# 11-LedIndicators.net
KiCad netlist of a schematic drawn in Altium Designer
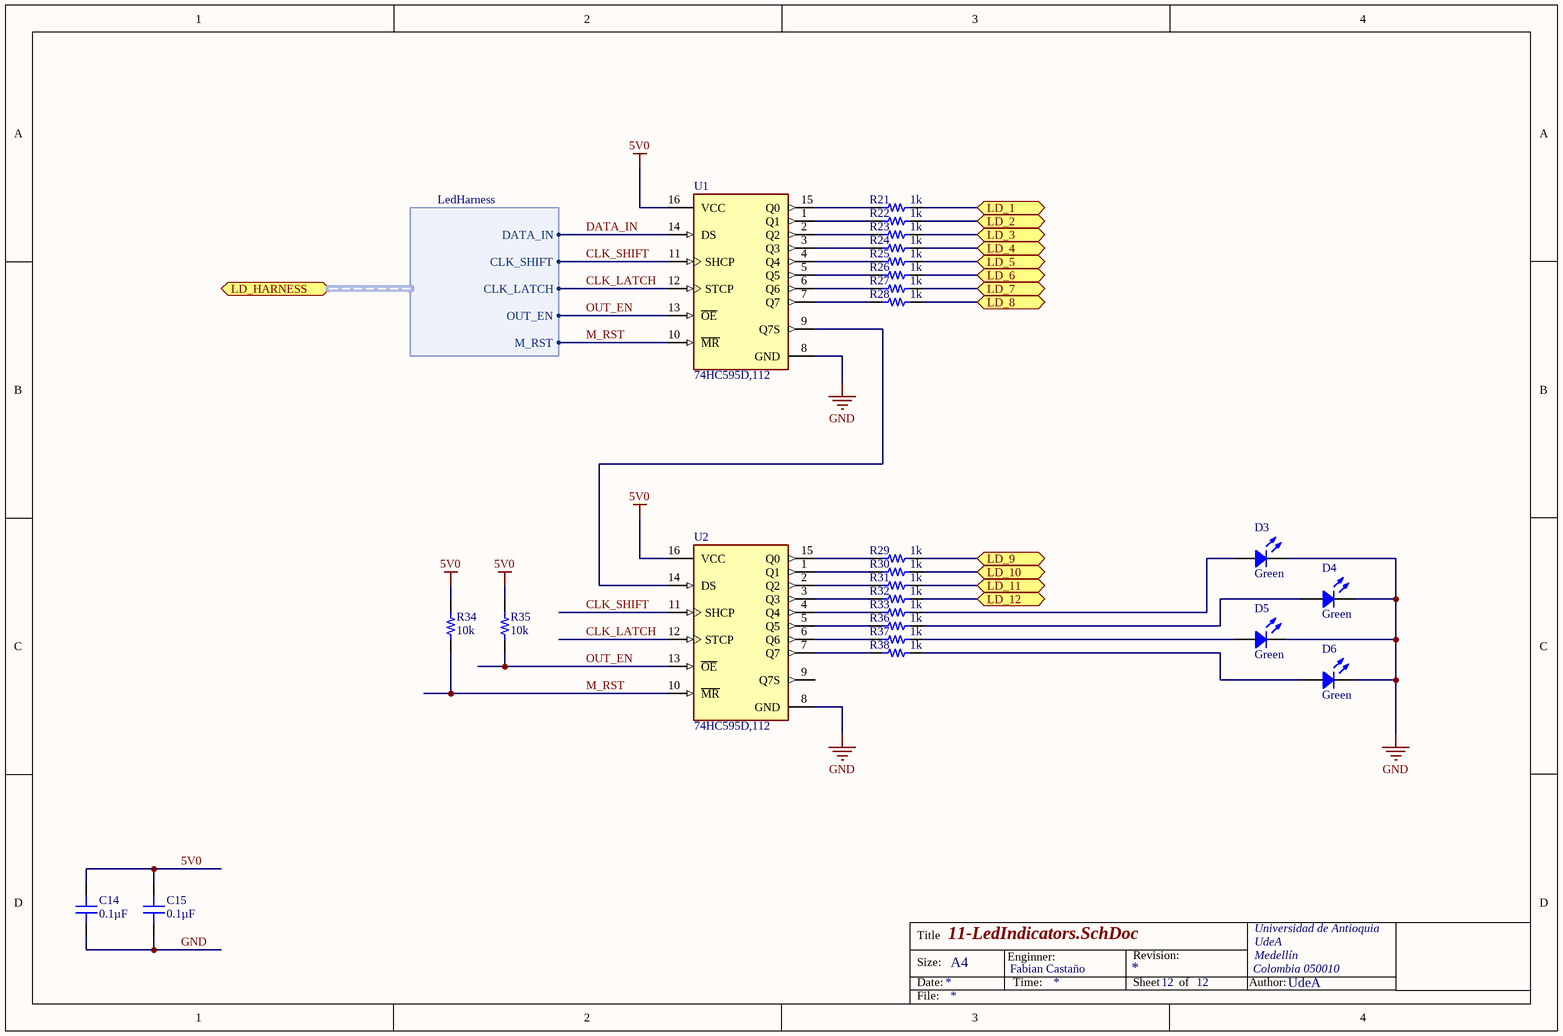
[diagram p0: 11-LedIndicators.SchDoc]

(export (version "E")
  (design (tool "Eeschema 10.0.6"))
  (components
    (comp (ref "C14")
      (value "0.1µF")
      (footprint "CAP 0805_2012")
      (description "CAP CER 0.1UF 50V X7R 0805")
      (fields (field (name "PART NUMBER") "C0805C104M5RACAUTO") (field (name "MANUFACTURER") "KEMET"))
      (libsource (lib "Celestial Altium Library - altium_library") (part "Capacitor"))
    )
    (comp (ref "C15")
      (value "0.1µF")
      (footprint "CAP 0805_2012")
      (description "CAP CER 0.1UF 50V X7R 0805")
      (fields (field (name "PART NUMBER") "C0805C104M5RACAUTO") (field (name "MANUFACTURER") "KEMET"))
      (libsource (lib "Celestial Altium Library - altium_library") (part "Capacitor"))
    )
    (comp (ref "D3")
      (value "Green")
      (footprint "LED 0805_2012 YELLOW")
      (description "LED YELLOW CLEAR CHIP SMD")
      (fields
        (field (name "PART NUMBER") "APT2012SYCK")
        (field (name "MANUFACTURER") "Kingbright")
        (field (name "LASTUPDATED") "12/04/2022 10:52:50 p. m.")
      )
      (libsource (lib "Celestial Altium Library - altium_library") (part "LED"))
    )
    (comp (ref "D4")
      (value "Green")
      (footprint "LED 0805_2012 YELLOW")
      (description "LED YELLOW CLEAR CHIP SMD")
      (fields
        (field (name "PART NUMBER") "APT2012SYCK")
        (field (name "MANUFACTURER") "Kingbright")
        (field (name "LASTUPDATED") "12/04/2022 10:52:50 p. m.")
      )
      (libsource (lib "Celestial Altium Library - altium_library") (part "LED"))
    )
    (comp (ref "D5")
      (value "Green")
      (footprint "LED 0805_2012 YELLOW")
      (description "LED YELLOW CLEAR CHIP SMD")
      (fields
        (field (name "PART NUMBER") "APT2012SYCK")
        (field (name "MANUFACTURER") "Kingbright")
        (field (name "LASTUPDATED") "12/04/2022 10:52:50 p. m.")
      )
      (libsource (lib "Celestial Altium Library - altium_library") (part "LED"))
    )
    (comp (ref "D6")
      (value "Green")
      (footprint "LED 0805_2012 YELLOW")
      (description "LED YELLOW CLEAR CHIP SMD")
      (fields
        (field (name "PART NUMBER") "APT2012SYCK")
        (field (name "MANUFACTURER") "Kingbright")
        (field (name "LASTUPDATED") "12/04/2022 10:52:50 p. m.")
      )
      (libsource (lib "Celestial Altium Library - altium_library") (part "LED"))
    )
    (comp (ref "R21")
      (value "1k")
      (footprint "RES 0805_2012")
      (description "RES SMD 1.47K OHM 1% 1/8W 0805")
      (fields (field (name "PART NUMBER") "RC0805FR-071K47L") (field (name "MANUFACTURER") "Yageo"))
      (libsource (lib "Celestial Altium Library - altium_library") (part "Resistor"))
    )
    (comp (ref "R22")
      (value "1k")
      (footprint "RES 0805_2012")
      (description "RES SMD 1.47K OHM 1% 1/8W 0805")
      (fields (field (name "PART NUMBER") "RC0805FR-071K47L") (field (name "MANUFACTURER") "Yageo"))
      (libsource (lib "Celestial Altium Library - altium_library") (part "Resistor"))
    )
    (comp (ref "R23")
      (value "1k")
      (footprint "RES 0805_2012")
      (description "RES SMD 1.47K OHM 1% 1/8W 0805")
      (fields (field (name "PART NUMBER") "RC0805FR-071K47L") (field (name "MANUFACTURER") "Yageo"))
      (libsource (lib "Celestial Altium Library - altium_library") (part "Resistor"))
    )
    (comp (ref "R24")
      (value "1k")
      (footprint "RES 0805_2012")
      (description "RES SMD 1.47K OHM 1% 1/8W 0805")
      (fields (field (name "PART NUMBER") "RC0805FR-071K47L") (field (name "MANUFACTURER") "Yageo"))
      (libsource (lib "Celestial Altium Library - altium_library") (part "Resistor"))
    )
    (comp (ref "R25")
      (value "1k")
      (footprint "RES 0805_2012")
      (description "RES SMD 1.47K OHM 1% 1/8W 0805")
      (fields (field (name "PART NUMBER") "RC0805FR-071K47L") (field (name "MANUFACTURER") "Yageo"))
      (libsource (lib "Celestial Altium Library - altium_library") (part "Resistor"))
    )
    (comp (ref "R26")
      (value "1k")
      (footprint "RES 0805_2012")
      (description "RES SMD 1.47K OHM 1% 1/8W 0805")
      (fields (field (name "PART NUMBER") "RC0805FR-071K47L") (field (name "MANUFACTURER") "Yageo"))
      (libsource (lib "Celestial Altium Library - altium_library") (part "Resistor"))
    )
    (comp (ref "R27")
      (value "1k")
      (footprint "RES 0805_2012")
      (description "RES SMD 1.47K OHM 1% 1/8W 0805")
      (fields (field (name "PART NUMBER") "RC0805FR-071K47L") (field (name "MANUFACTURER") "Yageo"))
      (libsource (lib "Celestial Altium Library - altium_library") (part "Resistor"))
    )
    (comp (ref "R28")
      (value "1k")
      (footprint "RES 0805_2012")
      (description "RES SMD 1.47K OHM 1% 1/8W 0805")
      (fields (field (name "PART NUMBER") "RC0805FR-071K47L") (field (name "MANUFACTURER") "Yageo"))
      (libsource (lib "Celestial Altium Library - altium_library") (part "Resistor"))
    )
    (comp (ref "R29")
      (value "1k")
      (footprint "RES 0805_2012")
      (description "RES SMD 1.47K OHM 1% 1/8W 0805")
      (fields (field (name "PART NUMBER") "RC0805FR-071K47L") (field (name "MANUFACTURER") "Yageo"))
      (libsource (lib "Celestial Altium Library - altium_library") (part "Resistor"))
    )
    (comp (ref "R30")
      (value "1k")
      (footprint "RES 0805_2012")
      (description "RES SMD 1.47K OHM 1% 1/8W 0805")
      (fields (field (name "PART NUMBER") "RC0805FR-071K47L") (field (name "MANUFACTURER") "Yageo"))
      (libsource (lib "Celestial Altium Library - altium_library") (part "Resistor"))
    )
    (comp (ref "R31")
      (value "1k")
      (footprint "RES 0805_2012")
      (description "RES SMD 1.47K OHM 1% 1/8W 0805")
      (fields (field (name "PART NUMBER") "RC0805FR-071K47L") (field (name "MANUFACTURER") "Yageo"))
      (libsource (lib "Celestial Altium Library - altium_library") (part "Resistor"))
    )
    (comp (ref "R32")
      (value "1k")
      (footprint "RES 0805_2012")
      (description "RES SMD 1.47K OHM 1% 1/8W 0805")
      (fields (field (name "PART NUMBER") "RC0805FR-071K47L") (field (name "MANUFACTURER") "Yageo"))
      (libsource (lib "Celestial Altium Library - altium_library") (part "Resistor"))
    )
    (comp (ref "R33")
      (value "1k")
      (footprint "RES 0805_2012")
      (description "RES SMD 1.47K OHM 1% 1/8W 0805")
      (fields (field (name "PART NUMBER") "RC0805FR-071K47L") (field (name "MANUFACTURER") "Yageo"))
      (libsource (lib "Celestial Altium Library - altium_library") (part "Resistor"))
    )
    (comp (ref "R34")
      (value "10k")
      (footprint "RES 0805_2012")
      (description "RES SMD 1.47K OHM 1% 1/8W 0805")
      (fields (field (name "PART NUMBER") "RC0805FR-071K47L") (field (name "MANUFACTURER") "Yageo"))
      (libsource (lib "Celestial Altium Library - altium_library") (part "Resistor"))
    )
    (comp (ref "R35")
      (value "10k")
      (footprint "RES 0805_2012")
      (description "RES SMD 1.47K OHM 1% 1/8W 0805")
      (fields (field (name "PART NUMBER") "RC0805FR-071K47L") (field (name "MANUFACTURER") "Yageo"))
      (libsource (lib "Celestial Altium Library - altium_library") (part "Resistor"))
    )
    (comp (ref "R36")
      (value "1k")
      (footprint "RES 0805_2012")
      (description "RES SMD 1.47K OHM 1% 1/8W 0805")
      (fields (field (name "PART NUMBER") "RC0805FR-071K47L") (field (name "MANUFACTURER") "Yageo"))
      (libsource (lib "Celestial Altium Library - altium_library") (part "Resistor"))
    )
    (comp (ref "R37")
      (value "1k")
      (footprint "RES 0805_2012")
      (description "RES SMD 1.47K OHM 1% 1/8W 0805")
      (fields (field (name "PART NUMBER") "RC0805FR-071K47L") (field (name "MANUFACTURER") "Yageo"))
      (libsource (lib "Celestial Altium Library - altium_library") (part "Resistor"))
    )
    (comp (ref "R38")
      (value "1k")
      (footprint "RES 0805_2012")
      (description "RES SMD 1.47K OHM 1% 1/8W 0805")
      (fields (field (name "PART NUMBER") "RC0805FR-071K47L") (field (name "MANUFACTURER") "Yageo"))
      (libsource (lib "Celestial Altium Library - altium_library") (part "Resistor"))
    )
    (comp (ref "U1")
      (value "74HC595D,112")
      (footprint "FP-SOT109-1-MFG")
      (description "IC SHIFT REGISTER 8BIT 16SOIC")
      (fields
        (field (name "OCTOPART") "https://octopart.com/74hc595d%2C112-nexperia-78737374")
        (field (name "MANUFACTURER") "Nexperia")
      )
      (libsource (lib "Altium Content Vault") (part "3b51a84c7bc4f00d385c04eb7d8d552"))
    )
    (comp (ref "U2")
      (value "74HC595D,112")
      (footprint "FP-SOT109-1-MFG")
      (description "IC SHIFT REGISTER 8BIT 16SOIC")
      (fields
        (field (name "OCTOPART") "https://octopart.com/74hc595d%2C112-nexperia-78737374")
        (field (name "MANUFACTURER") "Nexperia")
      )
      (libsource (lib "Altium Content Vault") (part "3b51a84c7bc4f00d385c04eb7d8d552"))
    )
  )
  (nets
    (net (code "2") (name "/CLK_LATCH") (class "Default")
      (node (ref "U1") (pin "12") (pinfunction "STCP_12") (pintype "input"))
      (node (ref "U2") (pin "12") (pinfunction "STCP_12") (pintype "input"))
    )
    (net (code "3") (name "/CLK_SHIFT") (class "Default")
      (node (ref "U1") (pin "11") (pinfunction "SHCP_11") (pintype "input"))
      (node (ref "U2") (pin "11") (pinfunction "SHCP_11") (pintype "input"))
    )
    (net (code "4") (name "/DATA_IN") (class "Default")
      (node (ref "U1") (pin "14") (pinfunction "DS_14") (pintype "input"))
    )
    (net (code "5") (name "/LD_1") (class "Default")
      (node (ref "R21") (pin "1") (pinfunction "1_1") (pintype "passive"))
    )
    (net (code "6") (name "/LD_2") (class "Default")
      (node (ref "R22") (pin "1") (pinfunction "1_1") (pintype "passive"))
    )
    (net (code "7") (name "/LD_3") (class "Default")
      (node (ref "R23") (pin "1") (pinfunction "1_1") (pintype "passive"))
    )
    (net (code "8") (name "/LD_4") (class "Default")
      (node (ref "R24") (pin "1") (pinfunction "1_1") (pintype "passive"))
    )
    (net (code "9") (name "/LD_5") (class "Default")
      (node (ref "R25") (pin "1") (pinfunction "1_1") (pintype "passive"))
    )
    (net (code "10") (name "/LD_6") (class "Default")
      (node (ref "R26") (pin "1") (pinfunction "1_1") (pintype "passive"))
    )
    (net (code "11") (name "/LD_7") (class "Default")
      (node (ref "R27") (pin "1") (pinfunction "1_1") (pintype "passive"))
    )
    (net (code "12") (name "/LD_8") (class "Default")
      (node (ref "R28") (pin "1") (pinfunction "1_1") (pintype "passive"))
    )
    (net (code "13") (name "/LD_9") (class "Default")
      (node (ref "R29") (pin "1") (pinfunction "1_1") (pintype "passive"))
    )
    (net (code "14") (name "/LD_10") (class "Default")
      (node (ref "R30") (pin "1") (pinfunction "1_1") (pintype "passive"))
    )
    (net (code "15") (name "/LD_11") (class "Default")
      (node (ref "R31") (pin "1") (pinfunction "1_1") (pintype "passive"))
    )
    (net (code "16") (name "/LD_12") (class "Default")
      (node (ref "R32") (pin "1") (pinfunction "1_1") (pintype "passive"))
    )
    (net (code "17") (name "/M_RST") (class "Default")
      (node (ref "R34") (pin "1") (pinfunction "1_1") (pintype "passive"))
      (node (ref "U1") (pin "10") (pinfunction "~{MR}_10") (pintype "input"))
      (node (ref "U2") (pin "10") (pinfunction "~{MR}_10") (pintype "input"))
    )
    (net (code "18") (name "/OUT_EN") (class "Default")
      (node (ref "R35") (pin "1") (pinfunction "1_1") (pintype "passive"))
      (node (ref "U1") (pin "13") (pinfunction "~{OE}_13") (pintype "input"))
      (node (ref "U2") (pin "13") (pinfunction "~{OE}_13") (pintype "input"))
    )
    (net (code "20") (name "5V0") (class "Default")
      (node (ref "C14") (pin "2") (pinfunction "2_2") (pintype "passive"))
      (node (ref "C15") (pin "2") (pinfunction "2_2") (pintype "passive"))
      (node (ref "R34") (pin "2") (pinfunction "2_2") (pintype "passive"))
      (node (ref "R35") (pin "2") (pinfunction "2_2") (pintype "passive"))
      (node (ref "U1") (pin "16") (pinfunction "VCC_16") (pintype "power_in"))
      (node (ref "U2") (pin "16") (pinfunction "VCC_16") (pintype "power_in"))
    )
    (net (code "21") (name "GND") (class "Default")
      (node (ref "C14") (pin "1") (pinfunction "1_1") (pintype "passive"))
      (node (ref "C15") (pin "1") (pinfunction "1_1") (pintype "passive"))
      (node (ref "D3") (pin "2") (pinfunction "2_2") (pintype "passive"))
      (node (ref "D4") (pin "2") (pinfunction "2_2") (pintype "passive"))
      (node (ref "D5") (pin "2") (pinfunction "2_2") (pintype "passive"))
      (node (ref "D6") (pin "2") (pinfunction "2_2") (pintype "passive"))
      (node (ref "U1") (pin "8") (pinfunction "GND_8") (pintype "power_in"))
      (node (ref "U2") (pin "8") (pinfunction "GND_8") (pintype "power_in"))
    )
    (net (code "22") (name "Net-(D3-Pad1)") (class "Default")
      (node (ref "D3") (pin "1") (pinfunction "1_1") (pintype "passive"))
      (node (ref "R33") (pin "1") (pinfunction "1_1") (pintype "passive"))
    )
    (net (code "23") (name "Net-(D4-Pad1)") (class "Default")
      (node (ref "D4") (pin "1") (pinfunction "1_1") (pintype "passive"))
      (node (ref "R36") (pin "1") (pinfunction "1_1") (pintype "passive"))
    )
    (net (code "24") (name "Net-(D5-Pad1)") (class "Default")
      (node (ref "D5") (pin "1") (pinfunction "1_1") (pintype "passive"))
      (node (ref "R37") (pin "1") (pinfunction "1_1") (pintype "passive"))
    )
    (net (code "25") (name "Net-(D6-Pad1)") (class "Default")
      (node (ref "D6") (pin "1") (pinfunction "1_1") (pintype "passive"))
      (node (ref "R38") (pin "1") (pinfunction "1_1") (pintype "passive"))
    )
    (net (code "26") (name "Net-(U1-Q0)") (class "Default")
      (node (ref "R21") (pin "2") (pinfunction "2_2") (pintype "passive"))
      (node (ref "U1") (pin "15") (pinfunction "Q0_15") (pintype "output"))
    )
    (net (code "27") (name "Net-(U1-Q1)") (class "Default")
      (node (ref "R22") (pin "2") (pinfunction "2_2") (pintype "passive"))
      (node (ref "U1") (pin "1") (pinfunction "Q1_1") (pintype "output"))
    )
    (net (code "28") (name "Net-(U1-Q2)") (class "Default")
      (node (ref "R23") (pin "2") (pinfunction "2_2") (pintype "passive"))
      (node (ref "U1") (pin "2") (pinfunction "Q2_2") (pintype "output"))
    )
    (net (code "29") (name "Net-(U1-Q3)") (class "Default")
      (node (ref "R24") (pin "2") (pinfunction "2_2") (pintype "passive"))
      (node (ref "U1") (pin "3") (pinfunction "Q3_3") (pintype "output"))
    )
    (net (code "30") (name "Net-(U1-Q4)") (class "Default")
      (node (ref "R25") (pin "2") (pinfunction "2_2") (pintype "passive"))
      (node (ref "U1") (pin "4") (pinfunction "Q4_4") (pintype "output"))
    )
    (net (code "31") (name "Net-(U1-Q5)") (class "Default")
      (node (ref "R26") (pin "2") (pinfunction "2_2") (pintype "passive"))
      (node (ref "U1") (pin "5") (pinfunction "Q5_5") (pintype "output"))
    )
    (net (code "32") (name "Net-(U1-Q6)") (class "Default")
      (node (ref "R27") (pin "2") (pinfunction "2_2") (pintype "passive"))
      (node (ref "U1") (pin "6") (pinfunction "Q6_6") (pintype "output"))
    )
    (net (code "33") (name "Net-(U1-Q7)") (class "Default")
      (node (ref "R28") (pin "2") (pinfunction "2_2") (pintype "passive"))
      (node (ref "U1") (pin "7") (pinfunction "Q7_7") (pintype "output"))
    )
    (net (code "34") (name "Net-(U1-Q7S)") (class "Default")
      (node (ref "U1") (pin "9") (pinfunction "Q7S_9") (pintype "output"))
      (node (ref "U2") (pin "14") (pinfunction "DS_14") (pintype "input"))
    )
    (net (code "35") (name "Net-(U2-Q0)") (class "Default")
      (node (ref "R29") (pin "2") (pinfunction "2_2") (pintype "passive"))
      (node (ref "U2") (pin "15") (pinfunction "Q0_15") (pintype "output"))
    )
    (net (code "36") (name "Net-(U2-Q1)") (class "Default")
      (node (ref "R30") (pin "2") (pinfunction "2_2") (pintype "passive"))
      (node (ref "U2") (pin "1") (pinfunction "Q1_1") (pintype "output"))
    )
    (net (code "37") (name "Net-(U2-Q2)") (class "Default")
      (node (ref "R31") (pin "2") (pinfunction "2_2") (pintype "passive"))
      (node (ref "U2") (pin "2") (pinfunction "Q2_2") (pintype "output"))
    )
    (net (code "38") (name "Net-(U2-Q3)") (class "Default")
      (node (ref "R32") (pin "2") (pinfunction "2_2") (pintype "passive"))
      (node (ref "U2") (pin "3") (pinfunction "Q3_3") (pintype "output"))
    )
    (net (code "39") (name "Net-(U2-Q4)") (class "Default")
      (node (ref "R33") (pin "2") (pinfunction "2_2") (pintype "passive"))
      (node (ref "U2") (pin "4") (pinfunction "Q4_4") (pintype "output"))
    )
    (net (code "40") (name "Net-(U2-Q5)") (class "Default")
      (node (ref "R36") (pin "2") (pinfunction "2_2") (pintype "passive"))
      (node (ref "U2") (pin "5") (pinfunction "Q5_5") (pintype "output"))
    )
    (net (code "41") (name "Net-(U2-Q6)") (class "Default")
      (node (ref "R37") (pin "2") (pinfunction "2_2") (pintype "passive"))
      (node (ref "U2") (pin "6") (pinfunction "Q6_6") (pintype "output"))
    )
    (net (code "42") (name "Net-(U2-Q7)") (class "Default")
      (node (ref "R38") (pin "2") (pinfunction "2_2") (pintype "passive"))
      (node (ref "U2") (pin "7") (pinfunction "Q7_7") (pintype "output"))
    )
    (net (code "43") (name "unconnected-(U2-Q7S-Pad9)") (class "Default")
      (node (ref "U2") (pin "9") (pinfunction "Q7S_9") (pintype "output"))
    )
  )
)
